# eib-64.net
KiCad netlist of a schematic drawn in EAGLE
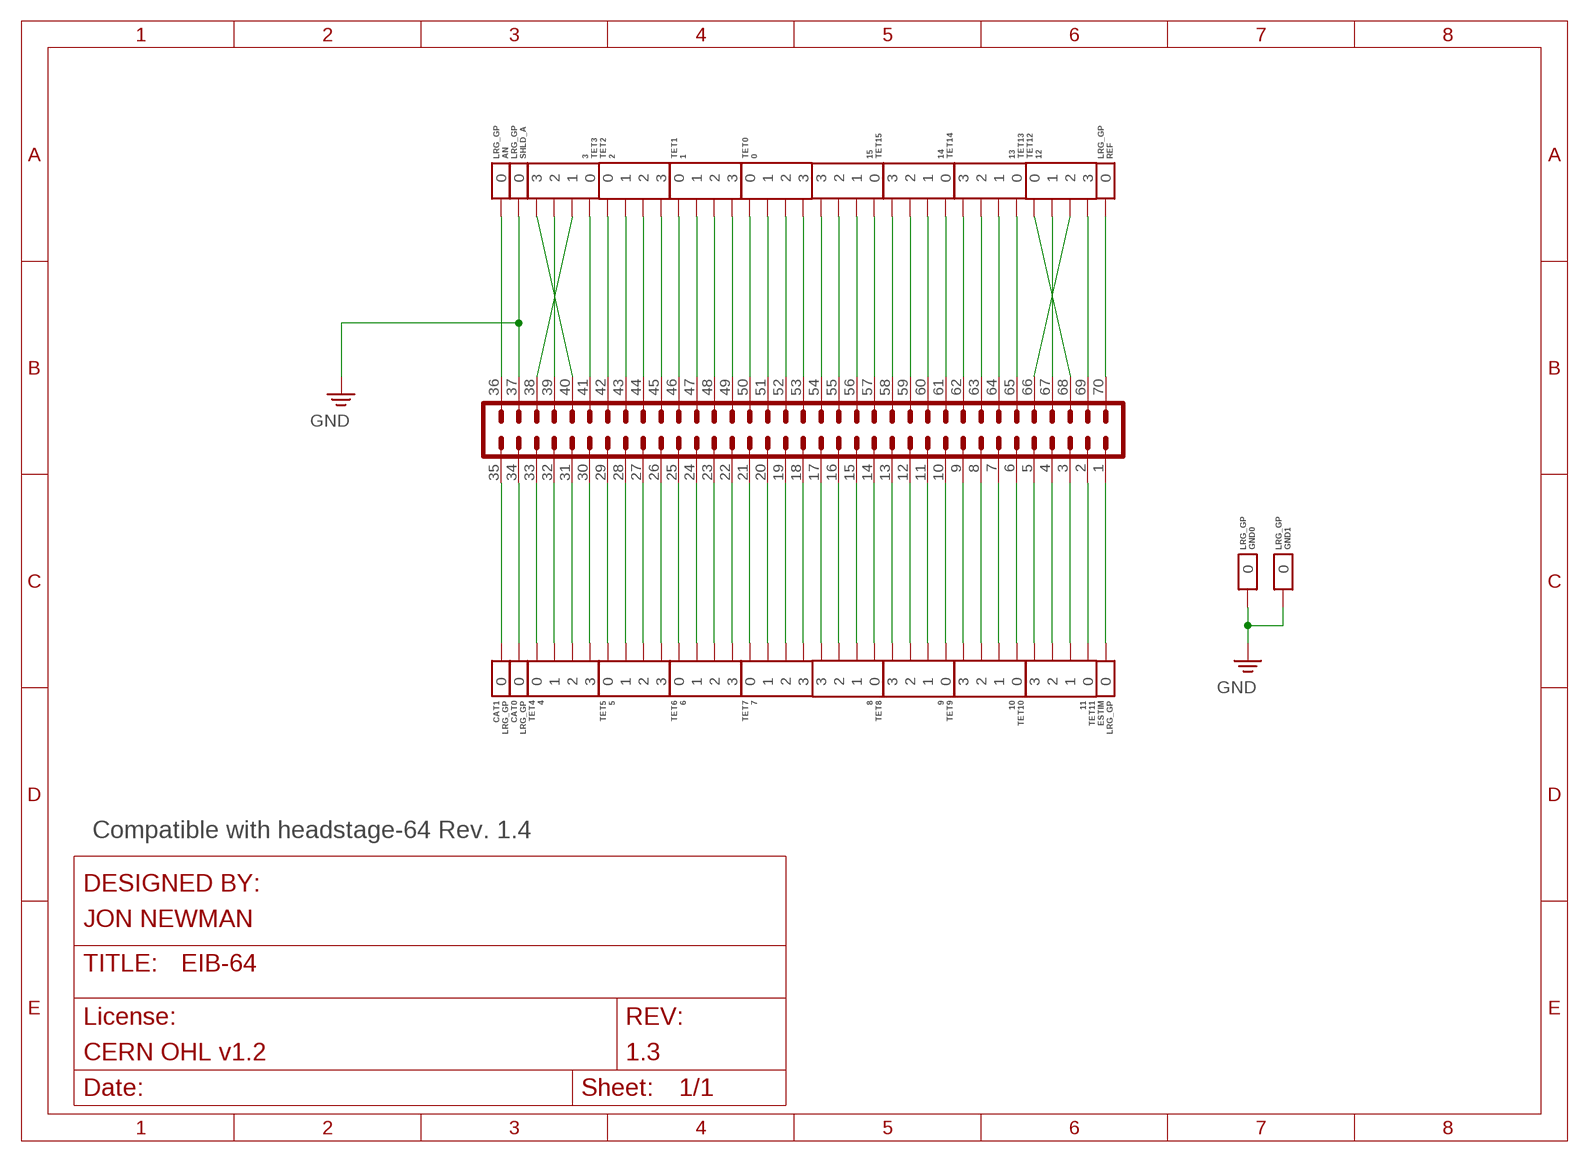
[diagram p0: schematic, sheet 1]

(export (version "E")
  (design (tool "Eeschema 10.0.6"))
  (components
    (comp (ref "AN")
      (value "LRG_GP")
      (footprint "eagle-import:GOLDPIN_0.5ID_0.7OD")
      (libsource (lib "eagle-import") (part "GOLDPIN_0.5ID_0.7OD"))
    )
    (comp (ref "CAT0")
      (value "LRG_GP")
      (footprint "eagle-import:GOLDPIN_0.5ID_0.7OD")
      (libsource (lib "eagle-import") (part "GOLDPIN_0.5ID_0.7OD"))
    )
    (comp (ref "CAT1")
      (value "LRG_GP")
      (footprint "eagle-import:GOLDPIN_0.5ID_0.7OD")
      (libsource (lib "eagle-import") (part "GOLDPIN_0.5ID_0.7OD"))
    )
    (comp (ref "ESTIM")
      (value "LRG_GP")
      (footprint "eagle-import:GOLDPIN_0.5ID_0.7OD")
      (libsource (lib "eagle-import") (part "GOLDPIN_0.5ID_0.7OD"))
    )
    (comp (ref "GND0")
      (value "LRG_GP")
      (footprint "eagle-import:GOLDPIN_0.5ID_0.7OD")
      (libsource (lib "eagle-import") (part "GOLDPIN_0.5ID_0.7OD"))
    )
    (comp (ref "GND1")
      (value "LRG_GP")
      (footprint "eagle-import:GOLDPIN_0.5ID_0.7OD")
      (libsource (lib "eagle-import") (part "GOLDPIN_0.5ID_0.7OD"))
    )
    (comp (ref "J1")
      (value "DF40-REC")
      (footprint "eagle-import:DF40-70REC")
      (libsource (lib "eagle-import") (part "PINHD-2X35_DF40REC"))
    )
    (comp (ref "REF")
      (value "LRG_GP")
      (footprint "eagle-import:GOLDPIN_0.5ID_0.7OD")
      (libsource (lib "eagle-import") (part "GOLDPIN_0.5ID_0.7OD"))
    )
    (comp (ref "SHLD_A")
      (value "LRG_GP")
      (footprint "eagle-import:GOLDPIN_0.5ID_0.7OD")
      (libsource (lib "eagle-import") (part "GOLDPIN_0.5ID_0.7OD"))
    )
    (comp (ref "TET0")
      (value "0")
      (footprint "eagle-import:TETRODE_0.3ID_LINEAR_MOUSE")
      (libsource (lib "eagle-import") (part "TETRODE_0.3ID_LINEAR_MOUSE"))
    )
    (comp (ref "TET1")
      (value "1")
      (footprint "eagle-import:TETRODE_0.3ID_LINEAR_MOUSE")
      (libsource (lib "eagle-import") (part "TETRODE_0.3ID_LINEAR_MOUSE"))
    )
    (comp (ref "TET2")
      (value "2")
      (footprint "eagle-import:TETRODE_0.3ID_LINEAR_MOUSE")
      (libsource (lib "eagle-import") (part "TETRODE_0.3ID_LINEAR_MOUSE"))
    )
    (comp (ref "TET3")
      (value "3")
      (footprint "eagle-import:TETRODE_0.3ID_LINEAR_MOUSE")
      (libsource (lib "eagle-import") (part "TETRODE_0.3ID_LINEAR_MOUSE"))
    )
    (comp (ref "TET4")
      (value "4")
      (footprint "eagle-import:TETRODE_0.3ID_LINEAR_MOUSE")
      (libsource (lib "eagle-import") (part "TETRODE_0.3ID_LINEAR_MOUSE"))
    )
    (comp (ref "TET5")
      (value "5")
      (footprint "eagle-import:TETRODE_0.3ID_LINEAR_MOUSE")
      (libsource (lib "eagle-import") (part "TETRODE_0.3ID_LINEAR_MOUSE"))
    )
    (comp (ref "TET6")
      (value "6")
      (footprint "eagle-import:TETRODE_0.3ID_LINEAR_MOUSE")
      (libsource (lib "eagle-import") (part "TETRODE_0.3ID_LINEAR_MOUSE"))
    )
    (comp (ref "TET7")
      (value "7")
      (footprint "eagle-import:TETRODE_0.3ID_LINEAR_MOUSE")
      (libsource (lib "eagle-import") (part "TETRODE_0.3ID_LINEAR_MOUSE"))
    )
    (comp (ref "TET8")
      (value "8")
      (footprint "eagle-import:TETRODE_0.3ID_LINEAR_MOUSE")
      (libsource (lib "eagle-import") (part "TETRODE_0.3ID_LINEAR_MOUSE"))
    )
    (comp (ref "TET9")
      (value "9")
      (footprint "eagle-import:TETRODE_0.3ID_LINEAR_MOUSE")
      (libsource (lib "eagle-import") (part "TETRODE_0.3ID_LINEAR_MOUSE"))
    )
    (comp (ref "TET10")
      (value "10")
      (footprint "eagle-import:TETRODE_0.3ID_LINEAR_MOUSE")
      (libsource (lib "eagle-import") (part "TETRODE_0.3ID_LINEAR_MOUSE"))
    )
    (comp (ref "TET11")
      (value "11")
      (footprint "eagle-import:TETRODE_0.3ID_LINEAR_MOUSE")
      (libsource (lib "eagle-import") (part "TETRODE_0.3ID_LINEAR_MOUSE"))
    )
    (comp (ref "TET12")
      (value "12")
      (footprint "eagle-import:TETRODE_0.3ID_LINEAR_MOUSE")
      (libsource (lib "eagle-import") (part "TETRODE_0.3ID_LINEAR_MOUSE"))
    )
    (comp (ref "TET13")
      (value "13")
      (footprint "eagle-import:TETRODE_0.3ID_LINEAR_MOUSE")
      (libsource (lib "eagle-import") (part "TETRODE_0.3ID_LINEAR_MOUSE"))
    )
    (comp (ref "TET14")
      (value "14")
      (footprint "eagle-import:TETRODE_0.3ID_LINEAR_MOUSE")
      (libsource (lib "eagle-import") (part "TETRODE_0.3ID_LINEAR_MOUSE"))
    )
    (comp (ref "TET15")
      (value "15")
      (footprint "eagle-import:TETRODE_0.3ID_LINEAR_MOUSE")
      (libsource (lib "eagle-import") (part "TETRODE_0.3ID_LINEAR_MOUSE"))
    )
  )
  (nets
    (net (code "1") (name "GND") (class "Default")
      (node (ref "GND0") (pin "P$1") (pinfunction "0_P$1") (pintype "bidirectional"))
      (node (ref "GND1") (pin "P$1") (pinfunction "0_P$1") (pintype "bidirectional"))
      (node (ref "J1") (pin "37") (pinfunction "37_37") (pintype "bidirectional"))
      (node (ref "SHLD_A") (pin "P$1") (pinfunction "0_P$1") (pintype "bidirectional"))
    )
    (net (code "2") (name "Net-(AN-0)") (class "Default")
      (node (ref "AN") (pin "P$1") (pinfunction "0_P$1") (pintype "bidirectional"))
      (node (ref "J1") (pin "36") (pinfunction "36_36") (pintype "bidirectional"))
    )
    (net (code "3") (name "Net-(CAT0-0)") (class "Default")
      (node (ref "CAT0") (pin "P$1") (pinfunction "0_P$1") (pintype "bidirectional"))
      (node (ref "J1") (pin "34") (pinfunction "34_34") (pintype "bidirectional"))
    )
    (net (code "4") (name "Net-(CAT1-0)") (class "Default")
      (node (ref "CAT1") (pin "P$1") (pinfunction "0_P$1") (pintype "bidirectional"))
      (node (ref "J1") (pin "35") (pinfunction "35_35") (pintype "bidirectional"))
    )
    (net (code "5") (name "Net-(ESTIM-0)") (class "Default")
      (node (ref "ESTIM") (pin "P$1") (pinfunction "0_P$1") (pintype "bidirectional"))
      (node (ref "J1") (pin "1") (pinfunction "1_1") (pintype "bidirectional"))
    )
    (net (code "6") (name "Net-(J1-Pad2)") (class "Default")
      (node (ref "J1") (pin "2") (pinfunction "2_2") (pintype "bidirectional"))
      (node (ref "TET11") (pin "0") (pinfunction "0_0") (pintype "bidirectional"))
    )
    (net (code "7") (name "Net-(J1-Pad3)") (class "Default")
      (node (ref "J1") (pin "3") (pinfunction "3_3") (pintype "bidirectional"))
      (node (ref "TET11") (pin "1") (pinfunction "1_1") (pintype "bidirectional"))
    )
    (net (code "8") (name "Net-(J1-Pad4)") (class "Default")
      (node (ref "J1") (pin "4") (pinfunction "4_4") (pintype "bidirectional"))
      (node (ref "TET11") (pin "2") (pinfunction "2_2") (pintype "bidirectional"))
    )
    (net (code "9") (name "Net-(J1-Pad5)") (class "Default")
      (node (ref "J1") (pin "5") (pinfunction "5_5") (pintype "bidirectional"))
      (node (ref "TET11") (pin "3") (pinfunction "3_3") (pintype "bidirectional"))
    )
    (net (code "10") (name "Net-(J1-Pad6)") (class "Default")
      (node (ref "J1") (pin "6") (pinfunction "6_6") (pintype "bidirectional"))
      (node (ref "TET10") (pin "0") (pinfunction "0_0") (pintype "bidirectional"))
    )
    (net (code "11") (name "Net-(J1-Pad7)") (class "Default")
      (node (ref "J1") (pin "7") (pinfunction "7_7") (pintype "bidirectional"))
      (node (ref "TET10") (pin "1") (pinfunction "1_1") (pintype "bidirectional"))
    )
    (net (code "12") (name "Net-(J1-Pad8)") (class "Default")
      (node (ref "J1") (pin "8") (pinfunction "8_8") (pintype "bidirectional"))
      (node (ref "TET10") (pin "2") (pinfunction "2_2") (pintype "bidirectional"))
    )
    (net (code "13") (name "Net-(J1-Pad9)") (class "Default")
      (node (ref "J1") (pin "9") (pinfunction "9_9") (pintype "bidirectional"))
      (node (ref "TET10") (pin "3") (pinfunction "3_3") (pintype "bidirectional"))
    )
    (net (code "14") (name "Net-(J1-Pad10)") (class "Default")
      (node (ref "J1") (pin "10") (pinfunction "10_10") (pintype "bidirectional"))
      (node (ref "TET9") (pin "0") (pinfunction "0_0") (pintype "bidirectional"))
    )
    (net (code "15") (name "Net-(J1-Pad11)") (class "Default")
      (node (ref "J1") (pin "11") (pinfunction "11_11") (pintype "bidirectional"))
      (node (ref "TET9") (pin "1") (pinfunction "1_1") (pintype "bidirectional"))
    )
    (net (code "16") (name "Net-(J1-Pad12)") (class "Default")
      (node (ref "J1") (pin "12") (pinfunction "12_12") (pintype "bidirectional"))
      (node (ref "TET9") (pin "2") (pinfunction "2_2") (pintype "bidirectional"))
    )
    (net (code "17") (name "Net-(J1-Pad13)") (class "Default")
      (node (ref "J1") (pin "13") (pinfunction "13_13") (pintype "bidirectional"))
      (node (ref "TET9") (pin "3") (pinfunction "3_3") (pintype "bidirectional"))
    )
    (net (code "18") (name "Net-(J1-Pad14)") (class "Default")
      (node (ref "J1") (pin "14") (pinfunction "14_14") (pintype "bidirectional"))
      (node (ref "TET8") (pin "0") (pinfunction "0_0") (pintype "bidirectional"))
    )
    (net (code "19") (name "Net-(J1-Pad15)") (class "Default")
      (node (ref "J1") (pin "15") (pinfunction "15_15") (pintype "bidirectional"))
      (node (ref "TET8") (pin "1") (pinfunction "1_1") (pintype "bidirectional"))
    )
    (net (code "20") (name "Net-(J1-Pad16)") (class "Default")
      (node (ref "J1") (pin "16") (pinfunction "16_16") (pintype "bidirectional"))
      (node (ref "TET8") (pin "2") (pinfunction "2_2") (pintype "bidirectional"))
    )
    (net (code "21") (name "Net-(J1-Pad17)") (class "Default")
      (node (ref "J1") (pin "17") (pinfunction "17_17") (pintype "bidirectional"))
      (node (ref "TET8") (pin "3") (pinfunction "3_3") (pintype "bidirectional"))
    )
    (net (code "22") (name "Net-(J1-Pad18)") (class "Default")
      (node (ref "J1") (pin "18") (pinfunction "18_18") (pintype "bidirectional"))
      (node (ref "TET7") (pin "3") (pinfunction "3_3") (pintype "bidirectional"))
    )
    (net (code "23") (name "Net-(J1-Pad19)") (class "Default")
      (node (ref "J1") (pin "19") (pinfunction "19_19") (pintype "bidirectional"))
      (node (ref "TET7") (pin "2") (pinfunction "2_2") (pintype "bidirectional"))
    )
    (net (code "24") (name "Net-(J1-Pad20)") (class "Default")
      (node (ref "J1") (pin "20") (pinfunction "20_20") (pintype "bidirectional"))
      (node (ref "TET7") (pin "1") (pinfunction "1_1") (pintype "bidirectional"))
    )
    (net (code "25") (name "Net-(J1-Pad21)") (class "Default")
      (node (ref "J1") (pin "21") (pinfunction "21_21") (pintype "bidirectional"))
      (node (ref "TET7") (pin "0") (pinfunction "0_0") (pintype "bidirectional"))
    )
    (net (code "26") (name "Net-(J1-Pad22)") (class "Default")
      (node (ref "J1") (pin "22") (pinfunction "22_22") (pintype "bidirectional"))
      (node (ref "TET6") (pin "3") (pinfunction "3_3") (pintype "bidirectional"))
    )
    (net (code "27") (name "Net-(J1-Pad23)") (class "Default")
      (node (ref "J1") (pin "23") (pinfunction "23_23") (pintype "bidirectional"))
      (node (ref "TET6") (pin "2") (pinfunction "2_2") (pintype "bidirectional"))
    )
    (net (code "28") (name "Net-(J1-Pad24)") (class "Default")
      (node (ref "J1") (pin "24") (pinfunction "24_24") (pintype "bidirectional"))
      (node (ref "TET6") (pin "1") (pinfunction "1_1") (pintype "bidirectional"))
    )
    (net (code "29") (name "Net-(J1-Pad25)") (class "Default")
      (node (ref "J1") (pin "25") (pinfunction "25_25") (pintype "bidirectional"))
      (node (ref "TET6") (pin "0") (pinfunction "0_0") (pintype "bidirectional"))
    )
    (net (code "30") (name "Net-(J1-Pad26)") (class "Default")
      (node (ref "J1") (pin "26") (pinfunction "26_26") (pintype "bidirectional"))
      (node (ref "TET5") (pin "3") (pinfunction "3_3") (pintype "bidirectional"))
    )
    (net (code "31") (name "Net-(J1-Pad27)") (class "Default")
      (node (ref "J1") (pin "27") (pinfunction "27_27") (pintype "bidirectional"))
      (node (ref "TET5") (pin "2") (pinfunction "2_2") (pintype "bidirectional"))
    )
    (net (code "32") (name "Net-(J1-Pad28)") (class "Default")
      (node (ref "J1") (pin "28") (pinfunction "28_28") (pintype "bidirectional"))
      (node (ref "TET5") (pin "1") (pinfunction "1_1") (pintype "bidirectional"))
    )
    (net (code "33") (name "Net-(J1-Pad29)") (class "Default")
      (node (ref "J1") (pin "29") (pinfunction "29_29") (pintype "bidirectional"))
      (node (ref "TET5") (pin "0") (pinfunction "0_0") (pintype "bidirectional"))
    )
    (net (code "34") (name "Net-(J1-Pad30)") (class "Default")
      (node (ref "J1") (pin "30") (pinfunction "30_30") (pintype "bidirectional"))
      (node (ref "TET4") (pin "3") (pinfunction "3_3") (pintype "bidirectional"))
    )
    (net (code "35") (name "Net-(J1-Pad31)") (class "Default")
      (node (ref "J1") (pin "31") (pinfunction "31_31") (pintype "bidirectional"))
      (node (ref "TET4") (pin "2") (pinfunction "2_2") (pintype "bidirectional"))
    )
    (net (code "36") (name "Net-(J1-Pad32)") (class "Default")
      (node (ref "J1") (pin "32") (pinfunction "32_32") (pintype "bidirectional"))
      (node (ref "TET4") (pin "1") (pinfunction "1_1") (pintype "bidirectional"))
    )
    (net (code "37") (name "Net-(J1-Pad33)") (class "Default")
      (node (ref "J1") (pin "33") (pinfunction "33_33") (pintype "bidirectional"))
      (node (ref "TET4") (pin "0") (pinfunction "0_0") (pintype "bidirectional"))
    )
    (net (code "38") (name "Net-(J1-Pad38)") (class "Default")
      (node (ref "J1") (pin "38") (pinfunction "38_38") (pintype "bidirectional"))
      (node (ref "TET3") (pin "1") (pinfunction "1_1") (pintype "bidirectional"))
    )
    (net (code "39") (name "Net-(J1-Pad39)") (class "Default")
      (node (ref "J1") (pin "39") (pinfunction "39_39") (pintype "bidirectional"))
      (node (ref "TET3") (pin "2") (pinfunction "2_2") (pintype "bidirectional"))
    )
    (net (code "40") (name "Net-(J1-Pad40)") (class "Default")
      (node (ref "J1") (pin "40") (pinfunction "40_40") (pintype "bidirectional"))
      (node (ref "TET3") (pin "3") (pinfunction "3_3") (pintype "bidirectional"))
    )
    (net (code "41") (name "Net-(J1-Pad41)") (class "Default")
      (node (ref "J1") (pin "41") (pinfunction "41_41") (pintype "bidirectional"))
      (node (ref "TET3") (pin "0") (pinfunction "0_0") (pintype "bidirectional"))
    )
    (net (code "42") (name "Net-(J1-Pad42)") (class "Default")
      (node (ref "J1") (pin "42") (pinfunction "42_42") (pintype "bidirectional"))
      (node (ref "TET2") (pin "0") (pinfunction "0_0") (pintype "bidirectional"))
    )
    (net (code "43") (name "Net-(J1-Pad43)") (class "Default")
      (node (ref "J1") (pin "43") (pinfunction "43_43") (pintype "bidirectional"))
      (node (ref "TET2") (pin "1") (pinfunction "1_1") (pintype "bidirectional"))
    )
    (net (code "44") (name "Net-(J1-Pad44)") (class "Default")
      (node (ref "J1") (pin "44") (pinfunction "44_44") (pintype "bidirectional"))
      (node (ref "TET2") (pin "2") (pinfunction "2_2") (pintype "bidirectional"))
    )
    (net (code "45") (name "Net-(J1-Pad45)") (class "Default")
      (node (ref "J1") (pin "45") (pinfunction "45_45") (pintype "bidirectional"))
      (node (ref "TET2") (pin "3") (pinfunction "3_3") (pintype "bidirectional"))
    )
    (net (code "46") (name "Net-(J1-Pad46)") (class "Default")
      (node (ref "J1") (pin "46") (pinfunction "46_46") (pintype "bidirectional"))
      (node (ref "TET1") (pin "0") (pinfunction "0_0") (pintype "bidirectional"))
    )
    (net (code "47") (name "Net-(J1-Pad47)") (class "Default")
      (node (ref "J1") (pin "47") (pinfunction "47_47") (pintype "bidirectional"))
      (node (ref "TET1") (pin "1") (pinfunction "1_1") (pintype "bidirectional"))
    )
    (net (code "48") (name "Net-(J1-Pad48)") (class "Default")
      (node (ref "J1") (pin "48") (pinfunction "48_48") (pintype "bidirectional"))
      (node (ref "TET1") (pin "2") (pinfunction "2_2") (pintype "bidirectional"))
    )
    (net (code "49") (name "Net-(J1-Pad49)") (class "Default")
      (node (ref "J1") (pin "49") (pinfunction "49_49") (pintype "bidirectional"))
      (node (ref "TET1") (pin "3") (pinfunction "3_3") (pintype "bidirectional"))
    )
    (net (code "50") (name "Net-(J1-Pad50)") (class "Default")
      (node (ref "J1") (pin "50") (pinfunction "50_50") (pintype "bidirectional"))
      (node (ref "TET0") (pin "0") (pinfunction "0_0") (pintype "bidirectional"))
    )
    (net (code "51") (name "Net-(J1-Pad51)") (class "Default")
      (node (ref "J1") (pin "51") (pinfunction "51_51") (pintype "bidirectional"))
      (node (ref "TET0") (pin "1") (pinfunction "1_1") (pintype "bidirectional"))
    )
    (net (code "52") (name "Net-(J1-Pad52)") (class "Default")
      (node (ref "J1") (pin "52") (pinfunction "52_52") (pintype "bidirectional"))
      (node (ref "TET0") (pin "2") (pinfunction "2_2") (pintype "bidirectional"))
    )
    (net (code "53") (name "Net-(J1-Pad53)") (class "Default")
      (node (ref "J1") (pin "53") (pinfunction "53_53") (pintype "bidirectional"))
      (node (ref "TET0") (pin "3") (pinfunction "3_3") (pintype "bidirectional"))
    )
    (net (code "54") (name "Net-(J1-Pad54)") (class "Default")
      (node (ref "J1") (pin "54") (pinfunction "54_54") (pintype "bidirectional"))
      (node (ref "TET15") (pin "3") (pinfunction "3_3") (pintype "bidirectional"))
    )
    (net (code "55") (name "Net-(J1-Pad55)") (class "Default")
      (node (ref "J1") (pin "55") (pinfunction "55_55") (pintype "bidirectional"))
      (node (ref "TET15") (pin "2") (pinfunction "2_2") (pintype "bidirectional"))
    )
    (net (code "56") (name "Net-(J1-Pad56)") (class "Default")
      (node (ref "J1") (pin "56") (pinfunction "56_56") (pintype "bidirectional"))
      (node (ref "TET15") (pin "1") (pinfunction "1_1") (pintype "bidirectional"))
    )
    (net (code "57") (name "Net-(J1-Pad57)") (class "Default")
      (node (ref "J1") (pin "57") (pinfunction "57_57") (pintype "bidirectional"))
      (node (ref "TET15") (pin "0") (pinfunction "0_0") (pintype "bidirectional"))
    )
    (net (code "58") (name "Net-(J1-Pad58)") (class "Default")
      (node (ref "J1") (pin "58") (pinfunction "58_58") (pintype "bidirectional"))
      (node (ref "TET14") (pin "3") (pinfunction "3_3") (pintype "bidirectional"))
    )
    (net (code "59") (name "Net-(J1-Pad59)") (class "Default")
      (node (ref "J1") (pin "59") (pinfunction "59_59") (pintype "bidirectional"))
      (node (ref "TET14") (pin "2") (pinfunction "2_2") (pintype "bidirectional"))
    )
    (net (code "60") (name "Net-(J1-Pad60)") (class "Default")
      (node (ref "J1") (pin "60") (pinfunction "60_60") (pintype "bidirectional"))
      (node (ref "TET14") (pin "1") (pinfunction "1_1") (pintype "bidirectional"))
    )
    (net (code "61") (name "Net-(J1-Pad61)") (class "Default")
      (node (ref "J1") (pin "61") (pinfunction "61_61") (pintype "bidirectional"))
      (node (ref "TET14") (pin "0") (pinfunction "0_0") (pintype "bidirectional"))
    )
    (net (code "62") (name "Net-(J1-Pad62)") (class "Default")
      (node (ref "J1") (pin "62") (pinfunction "62_62") (pintype "bidirectional"))
      (node (ref "TET13") (pin "3") (pinfunction "3_3") (pintype "bidirectional"))
    )
    (net (code "63") (name "Net-(J1-Pad63)") (class "Default")
      (node (ref "J1") (pin "63") (pinfunction "63_63") (pintype "bidirectional"))
      (node (ref "TET13") (pin "2") (pinfunction "2_2") (pintype "bidirectional"))
    )
    (net (code "64") (name "Net-(J1-Pad64)") (class "Default")
      (node (ref "J1") (pin "64") (pinfunction "64_64") (pintype "bidirectional"))
      (node (ref "TET13") (pin "1") (pinfunction "1_1") (pintype "bidirectional"))
    )
    (net (code "65") (name "Net-(J1-Pad65)") (class "Default")
      (node (ref "J1") (pin "65") (pinfunction "65_65") (pintype "bidirectional"))
      (node (ref "TET13") (pin "0") (pinfunction "0_0") (pintype "bidirectional"))
    )
    (net (code "66") (name "Net-(J1-Pad66)") (class "Default")
      (node (ref "J1") (pin "66") (pinfunction "66_66") (pintype "bidirectional"))
      (node (ref "TET12") (pin "2") (pinfunction "2_2") (pintype "bidirectional"))
    )
    (net (code "67") (name "Net-(J1-Pad67)") (class "Default")
      (node (ref "J1") (pin "67") (pinfunction "67_67") (pintype "bidirectional"))
      (node (ref "TET12") (pin "1") (pinfunction "1_1") (pintype "bidirectional"))
    )
    (net (code "68") (name "Net-(J1-Pad68)") (class "Default")
      (node (ref "J1") (pin "68") (pinfunction "68_68") (pintype "bidirectional"))
      (node (ref "TET12") (pin "0") (pinfunction "0_0") (pintype "bidirectional"))
    )
    (net (code "69") (name "Net-(J1-Pad69)") (class "Default")
      (node (ref "J1") (pin "69") (pinfunction "69_69") (pintype "bidirectional"))
      (node (ref "TET12") (pin "3") (pinfunction "3_3") (pintype "bidirectional"))
    )
    (net (code "70") (name "Net-(REF-0)") (class "Default")
      (node (ref "J1") (pin "70") (pinfunction "70_70") (pintype "bidirectional"))
      (node (ref "REF") (pin "P$1") (pinfunction "0_P$1") (pintype "bidirectional"))
    )
  )
)
